# Sheet1.net
KiCad netlist of a schematic drawn in Altium Designer
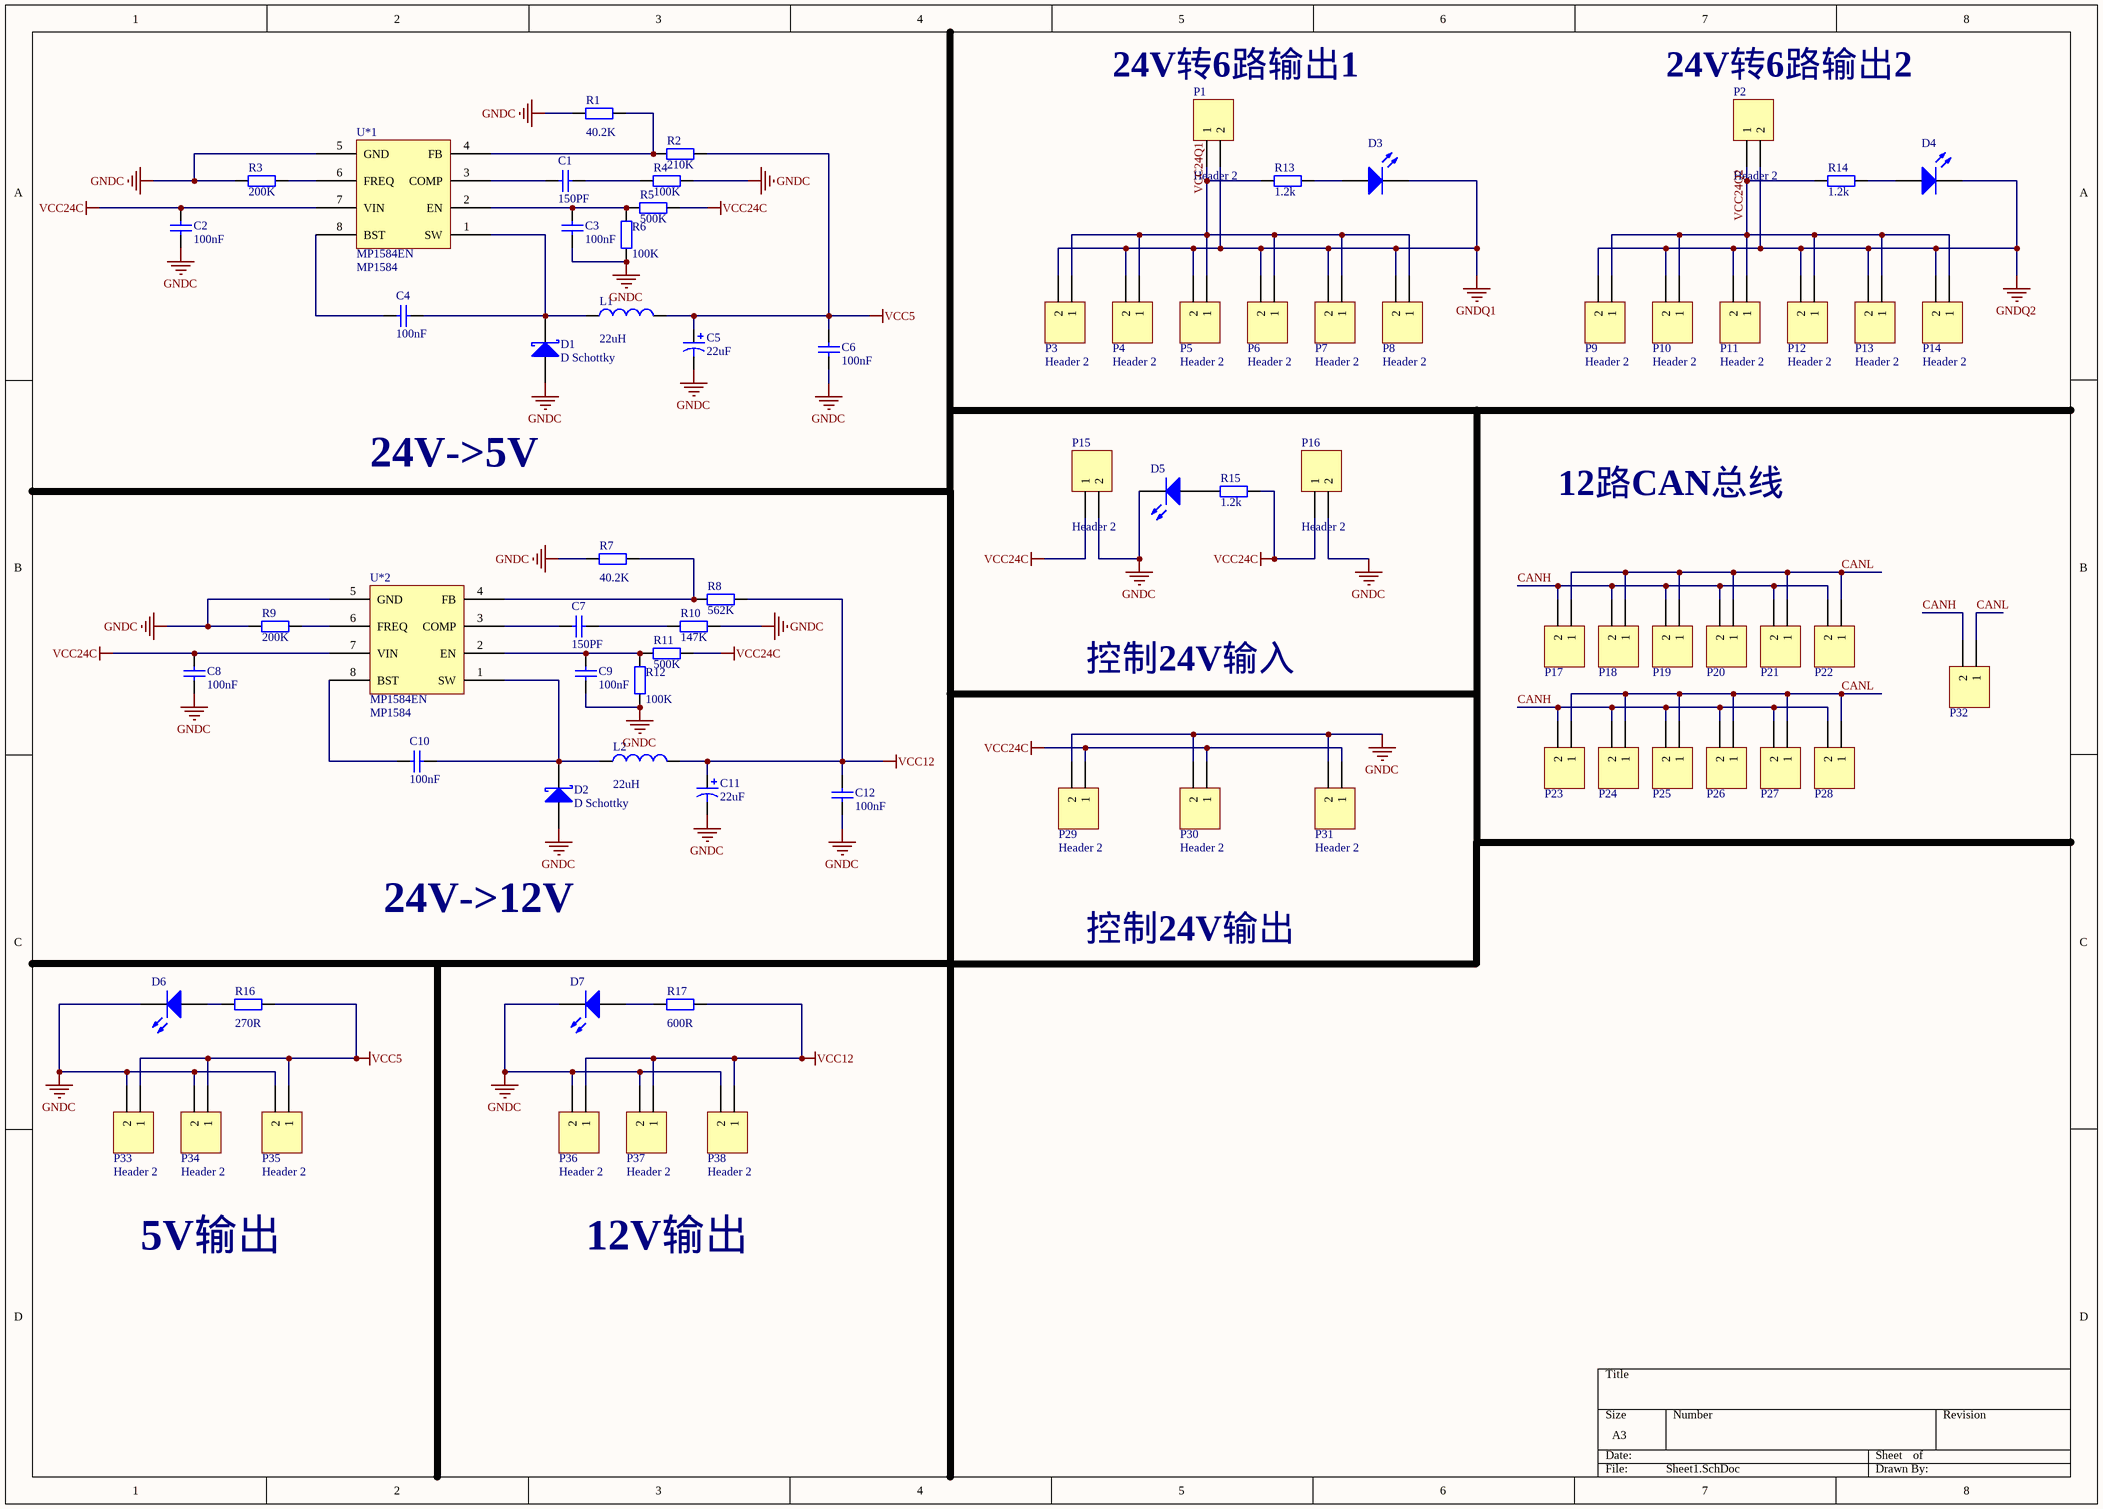
[diagram p0: Sheet1.SchDoc]

(export (version "E")
  (design (tool "Eeschema 10.0.6"))
  (components
    (comp (ref "C1")
      (value "150PF")
      (footprint "0603")
      (description "Capacitor")
      (fields (field (name "Comment") "Cap") (field (name "PUBLISHER") "Altium Limited"))
      (libsource (lib "Miscellaneous Devices") (part "Cap"))
    )
    (comp (ref "C2")
      (value "100nF")
      (footprint "0603")
      (description "Capacitor")
      (fields (field (name "Comment") "Cap") (field (name "PUBLISHER") "Altium Limited"))
      (libsource (lib "Miscellaneous Devices") (part "Cap"))
    )
    (comp (ref "C3")
      (value "100nF")
      (footprint "0603")
      (description "Capacitor")
      (fields (field (name "Comment") "Cap") (field (name "PUBLISHER") "Altium Limited"))
      (libsource (lib "Miscellaneous Devices") (part "Cap"))
    )
    (comp (ref "C4")
      (value "100nF")
      (footprint "0603")
      (description "Capacitor")
      (fields (field (name "Comment") "Cap") (field (name "PUBLISHER") "Altium Limited"))
      (libsource (lib "Miscellaneous Devices") (part "Cap"))
    )
    (comp (ref "C5")
      (value "22uF")
      (footprint "CAP_RVT1E220M0505")
      (description "Polarized Capacitor (Surface Mount)")
      (fields (field (name "Comment") "Cap Pol3") (field (name "PUBLISHER") "Altium Limited"))
      (libsource (lib "Miscellaneous Devices") (part "Cap Pol3"))
    )
    (comp (ref "C6")
      (value "100nF")
      (footprint "0603")
      (description "Capacitor")
      (fields (field (name "Comment") "Cap") (field (name "PUBLISHER") "Altium Limited"))
      (libsource (lib "Miscellaneous Devices") (part "Cap"))
    )
    (comp (ref "C7")
      (value "150PF")
      (footprint "0603")
      (description "Capacitor")
      (fields (field (name "Comment") "Cap") (field (name "PUBLISHER") "Altium Limited"))
      (libsource (lib "Miscellaneous Devices") (part "Cap"))
    )
    (comp (ref "C8")
      (value "100nF")
      (footprint "0603")
      (description "Capacitor")
      (fields (field (name "Comment") "Cap") (field (name "PUBLISHER") "Altium Limited"))
      (libsource (lib "Miscellaneous Devices") (part "Cap"))
    )
    (comp (ref "C9")
      (value "100nF")
      (footprint "0603")
      (description "Capacitor")
      (fields (field (name "Comment") "Cap") (field (name "PUBLISHER") "Altium Limited"))
      (libsource (lib "Miscellaneous Devices") (part "Cap"))
    )
    (comp (ref "C10")
      (value "100nF")
      (footprint "0603")
      (description "Capacitor")
      (fields (field (name "Comment") "Cap") (field (name "PUBLISHER") "Altium Limited"))
      (libsource (lib "Miscellaneous Devices") (part "Cap"))
    )
    (comp (ref "C11")
      (value "22uF")
      (footprint "CAP_RVT1E220M0505")
      (description "Polarized Capacitor (Surface Mount)")
      (fields (field (name "Comment") "Cap Pol3") (field (name "PUBLISHER") "Altium Limited"))
      (libsource (lib "Miscellaneous Devices") (part "Cap Pol3"))
    )
    (comp (ref "C12")
      (value "100nF")
      (footprint "0603")
      (description "Capacitor")
      (fields (field (name "Comment") "Cap") (field (name "PUBLISHER") "Altium Limited"))
      (libsource (lib "Miscellaneous Devices") (part "Cap"))
    )
    (comp (ref "D1")
      (value "D Schottky")
      (footprint "LC-SMB(DO-214AA)_S2")
      (description "Schottky Diode")
      (fields (field (name "PUBLISHER") "Altium Limited"))
      (libsource (lib "Miscellaneous Devices") (part "D Schottky"))
    )
    (comp (ref "D2")
      (value "D Schottky")
      (footprint "LC-SMB(DO-214AA)_S2")
      (description "Schottky Diode")
      (fields (field (name "PUBLISHER") "Altium Limited"))
      (libsource (lib "Miscellaneous Devices") (part "D Schottky"))
    )
    (comp (ref "D3")
      (value "LED0")
      (footprint "0603")
      (description "Typical INFRARED GaAs LED")
      (fields (field (name "PUBLISHER") "Altium Limited"))
      (libsource (lib "Miscellaneous Devices") (part "LED0"))
    )
    (comp (ref "D4")
      (value "LED0")
      (footprint "0603")
      (description "Typical INFRARED GaAs LED")
      (fields (field (name "PUBLISHER") "Altium Limited"))
      (libsource (lib "Miscellaneous Devices") (part "LED0"))
    )
    (comp (ref "D5")
      (value "LED0")
      (footprint "0603")
      (description "Typical INFRARED GaAs LED")
      (fields (field (name "PUBLISHER") "Altium Limited"))
      (libsource (lib "Miscellaneous Devices") (part "LED0"))
    )
    (comp (ref "D6")
      (value "LED0")
      (footprint "0603")
      (description "Typical INFRARED GaAs LED")
      (fields (field (name "PUBLISHER") "Altium Limited"))
      (libsource (lib "Miscellaneous Devices") (part "LED0"))
    )
    (comp (ref "D7")
      (value "LED0")
      (footprint "0603")
      (description "Typical INFRARED GaAs LED")
      (fields (field (name "PUBLISHER") "Altium Limited"))
      (libsource (lib "Miscellaneous Devices") (part "LED0"))
    )
    (comp (ref "L1")
      (value "22uH")
      (footprint "JSHC0650H220M")
      (description "Inductor")
      (fields (field (name "PUBLISHER") "Altium Limited"))
      (libsource (lib "Miscellaneous Devices") (part "Inductor"))
    )
    (comp (ref "L2")
      (value "22uH")
      (footprint "JSHC0650H220M")
      (description "Inductor")
      (fields (field (name "PUBLISHER") "Altium Limited"))
      (libsource (lib "Miscellaneous Devices") (part "Inductor"))
    )
    (comp (ref "P1")
      (value "Header 2")
      (footprint "TX60-LI-S")
      (description "Header, 2-Pin")
      (fields (field (name "PUBLISHER") "Altium Limited"))
      (libsource (lib "") (part "Header 2_1"))
    )
    (comp (ref "P2")
      (value "Header 2")
      (footprint "TX60-LI-S")
      (description "Header, 2-Pin")
      (fields (field (name "PUBLISHER") "Altium Limited"))
      (libsource (lib "") (part "Header 2_1"))
    )
    (comp (ref "P3")
      (value "Header 2")
      (footprint "XT30_LI")
      (description "Header, 2-Pin")
      (fields (field (name "PUBLISHER") "Altium Limited"))
      (libsource (lib "Miscellaneous Connectors") (part "Header 2"))
    )
    (comp (ref "P4")
      (value "Header 2")
      (footprint "XT30_LI")
      (description "Header, 2-Pin")
      (fields (field (name "PUBLISHER") "Altium Limited"))
      (libsource (lib "Miscellaneous Connectors") (part "Header 2"))
    )
    (comp (ref "P5")
      (value "Header 2")
      (footprint "XT30_LI")
      (description "Header, 2-Pin")
      (fields (field (name "PUBLISHER") "Altium Limited"))
      (libsource (lib "Miscellaneous Connectors") (part "Header 2"))
    )
    (comp (ref "P6")
      (value "Header 2")
      (footprint "XT30_LI")
      (description "Header, 2-Pin")
      (fields (field (name "PUBLISHER") "Altium Limited"))
      (libsource (lib "Miscellaneous Connectors") (part "Header 2"))
    )
    (comp (ref "P7")
      (value "Header 2")
      (footprint "XT30_LI")
      (description "Header, 2-Pin")
      (fields (field (name "PUBLISHER") "Altium Limited"))
      (libsource (lib "Miscellaneous Connectors") (part "Header 2"))
    )
    (comp (ref "P8")
      (value "Header 2")
      (footprint "XT30_LI")
      (description "Header, 2-Pin")
      (fields (field (name "PUBLISHER") "Altium Limited"))
      (libsource (lib "Miscellaneous Connectors") (part "Header 2"))
    )
    (comp (ref "P9")
      (value "Header 2")
      (footprint "XT30_LI")
      (description "Header, 2-Pin")
      (fields (field (name "PUBLISHER") "Altium Limited"))
      (libsource (lib "Miscellaneous Connectors") (part "Header 2"))
    )
    (comp (ref "P10")
      (value "Header 2")
      (footprint "XT30_LI")
      (description "Header, 2-Pin")
      (fields (field (name "PUBLISHER") "Altium Limited"))
      (libsource (lib "Miscellaneous Connectors") (part "Header 2"))
    )
    (comp (ref "P11")
      (value "Header 2")
      (footprint "XT30_LI")
      (description "Header, 2-Pin")
      (fields (field (name "PUBLISHER") "Altium Limited"))
      (libsource (lib "Miscellaneous Connectors") (part "Header 2"))
    )
    (comp (ref "P12")
      (value "Header 2")
      (footprint "XT30_LI")
      (description "Header, 2-Pin")
      (fields (field (name "PUBLISHER") "Altium Limited"))
      (libsource (lib "Miscellaneous Connectors") (part "Header 2"))
    )
    (comp (ref "P13")
      (value "Header 2")
      (footprint "XT30_LI")
      (description "Header, 2-Pin")
      (fields (field (name "PUBLISHER") "Altium Limited"))
      (libsource (lib "Miscellaneous Connectors") (part "Header 2"))
    )
    (comp (ref "P14")
      (value "Header 2")
      (footprint "XT30_LI")
      (description "Header, 2-Pin")
      (fields (field (name "PUBLISHER") "Altium Limited"))
      (libsource (lib "Miscellaneous Connectors") (part "Header 2"))
    )
    (comp (ref "P15")
      (value "Header 2")
      (footprint "TX60-LI-S")
      (description "Header, 2-Pin")
      (fields (field (name "PUBLISHER") "Altium Limited"))
      (libsource (lib "") (part "Header 2_1"))
    )
    (comp (ref "P16")
      (value "Header 2")
      (footprint "TX60-LI-S")
      (description "Header, 2-Pin")
      (fields (field (name "PUBLISHER") "Altium Limited"))
      (libsource (lib "") (part "Header 2_1"))
    )
    (comp (ref "P17")
      (value "Header 2")
      (footprint "GH1.25_2P")
      (description "Header, 2-Pin")
      (fields (field (name "PUBLISHER") "Altium Limited"))
      (libsource (lib "Miscellaneous Connectors") (part "Header 2"))
    )
    (comp (ref "P18")
      (value "Header 2")
      (footprint "GH1.25_2P")
      (description "Header, 2-Pin")
      (fields (field (name "PUBLISHER") "Altium Limited"))
      (libsource (lib "Miscellaneous Connectors") (part "Header 2"))
    )
    (comp (ref "P19")
      (value "Header 2")
      (footprint "GH1.25_2P")
      (description "Header, 2-Pin")
      (fields (field (name "PUBLISHER") "Altium Limited"))
      (libsource (lib "Miscellaneous Connectors") (part "Header 2"))
    )
    (comp (ref "P20")
      (value "Header 2")
      (footprint "GH1.25_2P")
      (description "Header, 2-Pin")
      (fields (field (name "PUBLISHER") "Altium Limited"))
      (libsource (lib "Miscellaneous Connectors") (part "Header 2"))
    )
    (comp (ref "P21")
      (value "Header 2")
      (footprint "GH1.25_2P")
      (description "Header, 2-Pin")
      (fields (field (name "PUBLISHER") "Altium Limited"))
      (libsource (lib "Miscellaneous Connectors") (part "Header 2"))
    )
    (comp (ref "P22")
      (value "Header 2")
      (footprint "GH1.25_2P")
      (description "Header, 2-Pin")
      (fields (field (name "PUBLISHER") "Altium Limited"))
      (libsource (lib "Miscellaneous Connectors") (part "Header 2"))
    )
    (comp (ref "P23")
      (value "Header 2")
      (footprint "GH1.25_2P")
      (description "Header, 2-Pin")
      (fields (field (name "PUBLISHER") "Altium Limited"))
      (libsource (lib "Miscellaneous Connectors") (part "Header 2"))
    )
    (comp (ref "P24")
      (value "Header 2")
      (footprint "GH1.25_2P")
      (description "Header, 2-Pin")
      (fields (field (name "PUBLISHER") "Altium Limited"))
      (libsource (lib "Miscellaneous Connectors") (part "Header 2"))
    )
    (comp (ref "P25")
      (value "Header 2")
      (footprint "GH1.25_2P")
      (description "Header, 2-Pin")
      (fields (field (name "PUBLISHER") "Altium Limited"))
      (libsource (lib "Miscellaneous Connectors") (part "Header 2"))
    )
    (comp (ref "P26")
      (value "Header 2")
      (footprint "GH1.25_2P")
      (description "Header, 2-Pin")
      (fields (field (name "PUBLISHER") "Altium Limited"))
      (libsource (lib "Miscellaneous Connectors") (part "Header 2"))
    )
    (comp (ref "P27")
      (value "Header 2")
      (footprint "GH1.25_2P")
      (description "Header, 2-Pin")
      (fields (field (name "PUBLISHER") "Altium Limited"))
      (libsource (lib "Miscellaneous Connectors") (part "Header 2"))
    )
    (comp (ref "P28")
      (value "Header 2")
      (footprint "GH1.25_2P")
      (description "Header, 2-Pin")
      (fields (field (name "PUBLISHER") "Altium Limited"))
      (libsource (lib "Miscellaneous Connectors") (part "Header 2"))
    )
    (comp (ref "P29")
      (value "Header 2")
      (footprint "XT30_LI")
      (description "Header, 2-Pin")
      (fields (field (name "PUBLISHER") "Altium Limited"))
      (libsource (lib "Miscellaneous Connectors") (part "Header 2"))
    )
    (comp (ref "P30")
      (value "Header 2")
      (footprint "XT30_LI")
      (description "Header, 2-Pin")
      (fields (field (name "PUBLISHER") "Altium Limited"))
      (libsource (lib "Miscellaneous Connectors") (part "Header 2"))
    )
    (comp (ref "P31")
      (value "Header 2")
      (footprint "XT30_LI")
      (description "Header, 2-Pin")
      (fields (field (name "PUBLISHER") "Altium Limited"))
      (libsource (lib "Miscellaneous Connectors") (part "Header 2"))
    )
    (comp (ref "P32")
      (value "Header 2")
      (footprint "GH1.25_2P")
      (description "Header, 2-Pin")
      (fields (field (name "PUBLISHER") "Altium Limited"))
      (libsource (lib "Miscellaneous Connectors") (part "Header 2"))
    )
    (comp (ref "P33")
      (value "Header 2")
      (footprint "XT30_LI")
      (description "Header, 2-Pin")
      (fields (field (name "PUBLISHER") "Altium Limited"))
      (libsource (lib "Miscellaneous Connectors") (part "Header 2"))
    )
    (comp (ref "P34")
      (value "Header 2")
      (footprint "XT30_LI")
      (description "Header, 2-Pin")
      (fields (field (name "PUBLISHER") "Altium Limited"))
      (libsource (lib "Miscellaneous Connectors") (part "Header 2"))
    )
    (comp (ref "P35")
      (value "Header 2")
      (footprint "XT30_LI")
      (description "Header, 2-Pin")
      (fields (field (name "PUBLISHER") "Altium Limited"))
      (libsource (lib "Miscellaneous Connectors") (part "Header 2"))
    )
    (comp (ref "P36")
      (value "Header 2")
      (footprint "XT30_LI")
      (description "Header, 2-Pin")
      (fields (field (name "PUBLISHER") "Altium Limited"))
      (libsource (lib "Miscellaneous Connectors") (part "Header 2"))
    )
    (comp (ref "P37")
      (value "Header 2")
      (footprint "XT30_LI")
      (description "Header, 2-Pin")
      (fields (field (name "PUBLISHER") "Altium Limited"))
      (libsource (lib "Miscellaneous Connectors") (part "Header 2"))
    )
    (comp (ref "P38")
      (value "Header 2")
      (footprint "XT30_LI")
      (description "Header, 2-Pin")
      (fields (field (name "PUBLISHER") "Altium Limited"))
      (libsource (lib "Miscellaneous Connectors") (part "Header 2"))
    )
    (comp (ref "R1")
      (value "40.2K")
      (footprint "0603")
      (description "Resistor")
      (fields (field (name "Comment") "Res2") (field (name "PUBLISHER") "Altium Limited"))
      (libsource (lib "") (part "Res2_1"))
    )
    (comp (ref "R2")
      (value "210K")
      (footprint "0603")
      (description "Resistor")
      (fields (field (name "Comment") "Res2") (field (name "PUBLISHER") "Altium Limited"))
      (libsource (lib "") (part "Res2_1"))
    )
    (comp (ref "R3")
      (value "200K")
      (footprint "0603")
      (description "Resistor")
      (fields (field (name "Comment") "Res2") (field (name "PUBLISHER") "Altium Limited"))
      (libsource (lib "") (part "Res2_1"))
    )
    (comp (ref "R4")
      (value "100K")
      (footprint "0603")
      (description "Resistor")
      (fields (field (name "Comment") "Res2") (field (name "PUBLISHER") "Altium Limited"))
      (libsource (lib "") (part "Res2_1"))
    )
    (comp (ref "R5")
      (value "500K")
      (footprint "0603")
      (description "Resistor")
      (fields (field (name "Comment") "Res2") (field (name "PUBLISHER") "Altium Limited"))
      (libsource (lib "") (part "Res2_1"))
    )
    (comp (ref "R6")
      (value "100K")
      (footprint "0603")
      (description "Resistor")
      (fields (field (name "Comment") "Res2") (field (name "PUBLISHER") "Altium Limited"))
      (libsource (lib "") (part "Res2_2"))
    )
    (comp (ref "R7")
      (value "40.2K")
      (footprint "0603")
      (description "Resistor")
      (fields (field (name "Comment") "Res2") (field (name "PUBLISHER") "Altium Limited"))
      (libsource (lib "") (part "Res2_1"))
    )
    (comp (ref "R8")
      (value "562K")
      (footprint "0603")
      (description "Resistor")
      (fields (field (name "Comment") "Res2") (field (name "PUBLISHER") "Altium Limited"))
      (libsource (lib "") (part "Res2_1"))
    )
    (comp (ref "R9")
      (value "200K")
      (footprint "0603")
      (description "Resistor")
      (fields (field (name "Comment") "Res2") (field (name "PUBLISHER") "Altium Limited"))
      (libsource (lib "") (part "Res2_1"))
    )
    (comp (ref "R10")
      (value "147K")
      (footprint "0603")
      (description "Resistor")
      (fields (field (name "Comment") "Res2") (field (name "PUBLISHER") "Altium Limited"))
      (libsource (lib "") (part "Res2_1"))
    )
    (comp (ref "R11")
      (value "500K")
      (footprint "0603")
      (description "Resistor")
      (fields (field (name "Comment") "Res2") (field (name "PUBLISHER") "Altium Limited"))
      (libsource (lib "") (part "Res2_1"))
    )
    (comp (ref "R12")
      (value "100K")
      (footprint "0603")
      (description "Resistor")
      (fields (field (name "Comment") "Res2") (field (name "PUBLISHER") "Altium Limited"))
      (libsource (lib "") (part "Res2_2"))
    )
    (comp (ref "R13")
      (value "1.2k")
      (footprint "0603")
      (description "Resistor")
      (fields (field (name "Comment") "Res2") (field (name "PUBLISHER") "Altium Limited"))
      (libsource (lib "Miscellaneous Devices") (part "Res2"))
    )
    (comp (ref "R14")
      (value "1.2k")
      (footprint "0603")
      (description "Resistor")
      (fields (field (name "Comment") "Res2") (field (name "PUBLISHER") "Altium Limited"))
      (libsource (lib "Miscellaneous Devices") (part "Res2"))
    )
    (comp (ref "R15")
      (value "1.2k")
      (footprint "0603")
      (description "Resistor")
      (fields (field (name "Comment") "Res2") (field (name "PUBLISHER") "Altium Limited"))
      (libsource (lib "") (part "Res2_1"))
    )
    (comp (ref "R16")
      (value "270R")
      (footprint "0603")
      (description "Resistor")
      (fields (field (name "Comment") "Res2") (field (name "PUBLISHER") "Altium Limited"))
      (libsource (lib "") (part "Res2_1"))
    )
    (comp (ref "R17")
      (value "600R")
      (footprint "0603")
      (description "Resistor")
      (fields (field (name "Comment") "Res2") (field (name "PUBLISHER") "Altium Limited"))
      (libsource (lib "") (part "Res2_1"))
    )
    (comp (ref "U*1")
      (value "MP1584")
      (footprint "MP1584EN_SOIC8E")
      (libsource (lib "Schlib1") (part "MP1584"))
    )
    (comp (ref "U*2")
      (value "MP1584")
      (footprint "MP1584EN_SOIC8E")
      (libsource (lib "Schlib1") (part "MP1584"))
    )
  )
  (nets
    (net (code "1") (name "/CANH") (class "Default")
      (node (ref "P17") (pin "2") (pinfunction "2_2") (pintype "passive"))
      (node (ref "P18") (pin "2") (pinfunction "2_2") (pintype "passive"))
      (node (ref "P19") (pin "2") (pinfunction "2_2") (pintype "passive"))
      (node (ref "P20") (pin "2") (pinfunction "2_2") (pintype "passive"))
      (node (ref "P21") (pin "2") (pinfunction "2_2") (pintype "passive"))
      (node (ref "P22") (pin "2") (pinfunction "2_2") (pintype "passive"))
      (node (ref "P23") (pin "2") (pinfunction "2_2") (pintype "passive"))
      (node (ref "P24") (pin "2") (pinfunction "2_2") (pintype "passive"))
      (node (ref "P25") (pin "2") (pinfunction "2_2") (pintype "passive"))
      (node (ref "P26") (pin "2") (pinfunction "2_2") (pintype "passive"))
      (node (ref "P27") (pin "2") (pinfunction "2_2") (pintype "passive"))
      (node (ref "P28") (pin "2") (pinfunction "2_2") (pintype "passive"))
      (node (ref "P32") (pin "2") (pinfunction "2_2") (pintype "passive"))
    )
    (net (code "2") (name "/CANL") (class "Default")
      (node (ref "P17") (pin "1") (pinfunction "1_1") (pintype "passive"))
      (node (ref "P18") (pin "1") (pinfunction "1_1") (pintype "passive"))
      (node (ref "P19") (pin "1") (pinfunction "1_1") (pintype "passive"))
      (node (ref "P20") (pin "1") (pinfunction "1_1") (pintype "passive"))
      (node (ref "P21") (pin "1") (pinfunction "1_1") (pintype "passive"))
      (node (ref "P22") (pin "1") (pinfunction "1_1") (pintype "passive"))
      (node (ref "P23") (pin "1") (pinfunction "1_1") (pintype "passive"))
      (node (ref "P24") (pin "1") (pinfunction "1_1") (pintype "passive"))
      (node (ref "P25") (pin "1") (pinfunction "1_1") (pintype "passive"))
      (node (ref "P26") (pin "1") (pinfunction "1_1") (pintype "passive"))
      (node (ref "P27") (pin "1") (pinfunction "1_1") (pintype "passive"))
      (node (ref "P28") (pin "1") (pinfunction "1_1") (pintype "passive"))
      (node (ref "P32") (pin "1") (pinfunction "1_1") (pintype "passive"))
    )
    (net (code "3") (name "/VCC24Q1") (class "Default")
      (node (ref "P1") (pin "1") (pinfunction "1_1") (pintype "passive"))
      (node (ref "P3") (pin "1") (pinfunction "1_1") (pintype "passive"))
      (node (ref "P4") (pin "1") (pinfunction "1_1") (pintype "passive"))
      (node (ref "P5") (pin "1") (pinfunction "1_1") (pintype "passive"))
      (node (ref "P6") (pin "1") (pinfunction "1_1") (pintype "passive"))
      (node (ref "P7") (pin "1") (pinfunction "1_1") (pintype "passive"))
      (node (ref "P8") (pin "1") (pinfunction "1_1") (pintype "passive"))
      (node (ref "R13") (pin "1") (pinfunction "1_1") (pintype "passive"))
    )
    (net (code "4") (name "/VCC24Q2") (class "Default")
      (node (ref "P10") (pin "1") (pinfunction "1_1") (pintype "passive"))
      (node (ref "P11") (pin "1") (pinfunction "1_1") (pintype "passive"))
      (node (ref "P12") (pin "1") (pinfunction "1_1") (pintype "passive"))
      (node (ref "P13") (pin "1") (pinfunction "1_1") (pintype "passive"))
      (node (ref "P14") (pin "1") (pinfunction "1_1") (pintype "passive"))
      (node (ref "P2") (pin "1") (pinfunction "1_1") (pintype "passive"))
      (node (ref "P9") (pin "1") (pinfunction "1_1") (pintype "passive"))
      (node (ref "R14") (pin "1") (pinfunction "1_1") (pintype "passive"))
    )
    (net (code "5") (name "GNDC") (class "Default")
      (node (ref "C11") (pin "2") (pinfunction "2_2") (pintype "passive"))
      (node (ref "C12") (pin "1") (pinfunction "1_1") (pintype "passive"))
      (node (ref "C2") (pin "1") (pinfunction "1_1") (pintype "passive"))
      (node (ref "C3") (pin "1") (pinfunction "1_1") (pintype "passive"))
      (node (ref "C5") (pin "2") (pinfunction "2_2") (pintype "passive"))
      (node (ref "C6") (pin "1") (pinfunction "1_1") (pintype "passive"))
      (node (ref "C8") (pin "1") (pinfunction "1_1") (pintype "passive"))
      (node (ref "C9") (pin "1") (pinfunction "1_1") (pintype "passive"))
      (node (ref "D1") (pin "1") (pinfunction "A_1") (pintype "passive"))
      (node (ref "D2") (pin "1") (pinfunction "A_1") (pintype "passive"))
      (node (ref "D5") (pin "2") (pinfunction "K_2") (pintype "passive"))
      (node (ref "D6") (pin "2") (pinfunction "K_2") (pintype "passive"))
      (node (ref "D7") (pin "2") (pinfunction "K_2") (pintype "passive"))
      (node (ref "P15") (pin "2") (pinfunction "2_2") (pintype "passive"))
      (node (ref "P16") (pin "2") (pinfunction "2_2") (pintype "passive"))
      (node (ref "P29") (pin "2") (pinfunction "2_2") (pintype "passive"))
      (node (ref "P30") (pin "2") (pinfunction "2_2") (pintype "passive"))
      (node (ref "P31") (pin "2") (pinfunction "2_2") (pintype "passive"))
      (node (ref "P33") (pin "2") (pinfunction "2_2") (pintype "passive"))
      (node (ref "P34") (pin "2") (pinfunction "2_2") (pintype "passive"))
      (node (ref "P35") (pin "2") (pinfunction "2_2") (pintype "passive"))
      (node (ref "P36") (pin "2") (pinfunction "2_2") (pintype "passive"))
      (node (ref "P37") (pin "2") (pinfunction "2_2") (pintype "passive"))
      (node (ref "P38") (pin "2") (pinfunction "2_2") (pintype "passive"))
      (node (ref "R1") (pin "2") (pinfunction "2_2") (pintype "passive"))
      (node (ref "R10") (pin "1") (pinfunction "1_1") (pintype "passive"))
      (node (ref "R12") (pin "1") (pinfunction "1_1") (pintype "passive"))
      (node (ref "R3") (pin "2") (pinfunction "2_2") (pintype "passive"))
      (node (ref "R4") (pin "1") (pinfunction "1_1") (pintype "passive"))
      (node (ref "R6") (pin "1") (pinfunction "1_1") (pintype "passive"))
      (node (ref "R7") (pin "2") (pinfunction "2_2") (pintype "passive"))
      (node (ref "R9") (pin "2") (pinfunction "2_2") (pintype "passive"))
      (node (ref "U*1") (pin "5") (pinfunction "GND_5") (pintype "passive"))
      (node (ref "U*2") (pin "5") (pinfunction "GND_5") (pintype "passive"))
    )
    (net (code "6") (name "GNDQ1") (class "Default")
      (node (ref "D3") (pin "2") (pinfunction "K_2") (pintype "passive"))
      (node (ref "P1") (pin "2") (pinfunction "2_2") (pintype "passive"))
      (node (ref "P3") (pin "2") (pinfunction "2_2") (pintype "passive"))
      (node (ref "P4") (pin "2") (pinfunction "2_2") (pintype "passive"))
      (node (ref "P5") (pin "2") (pinfunction "2_2") (pintype "passive"))
      (node (ref "P6") (pin "2") (pinfunction "2_2") (pintype "passive"))
      (node (ref "P7") (pin "2") (pinfunction "2_2") (pintype "passive"))
      (node (ref "P8") (pin "2") (pinfunction "2_2") (pintype "passive"))
    )
    (net (code "7") (name "GNDQ2") (class "Default")
      (node (ref "D4") (pin "2") (pinfunction "K_2") (pintype "passive"))
      (node (ref "P10") (pin "2") (pinfunction "2_2") (pintype "passive"))
      (node (ref "P11") (pin "2") (pinfunction "2_2") (pintype "passive"))
      (node (ref "P12") (pin "2") (pinfunction "2_2") (pintype "passive"))
      (node (ref "P13") (pin "2") (pinfunction "2_2") (pintype "passive"))
      (node (ref "P14") (pin "2") (pinfunction "2_2") (pintype "passive"))
      (node (ref "P2") (pin "2") (pinfunction "2_2") (pintype "passive"))
      (node (ref "P9") (pin "2") (pinfunction "2_2") (pintype "passive"))
    )
    (net (code "8") (name "Net-(C1-Pad1)") (class "Default")
      (node (ref "C1") (pin "1") (pinfunction "1_1") (pintype "passive"))
      (node (ref "R4") (pin "2") (pinfunction "2_2") (pintype "passive"))
    )
    (net (code "9") (name "Net-(C7-Pad1)") (class "Default")
      (node (ref "C7") (pin "1") (pinfunction "1_1") (pintype "passive"))
      (node (ref "R10") (pin "2") (pinfunction "2_2") (pintype "passive"))
    )
    (net (code "10") (name "Net-(D1-K)") (class "Default")
      (node (ref "C4") (pin "1") (pinfunction "1_1") (pintype "passive"))
      (node (ref "D1") (pin "2") (pinfunction "K_2") (pintype "passive"))
      (node (ref "L1") (pin "1") (pinfunction "1_1") (pintype "passive"))
      (node (ref "U*1") (pin "1") (pinfunction "SW_1") (pintype "passive"))
    )
    (net (code "11") (name "Net-(D2-K)") (class "Default")
      (node (ref "C10") (pin "1") (pinfunction "1_1") (pintype "passive"))
      (node (ref "D2") (pin "2") (pinfunction "K_2") (pintype "passive"))
      (node (ref "L2") (pin "1") (pinfunction "1_1") (pintype "passive"))
      (node (ref "U*2") (pin "1") (pinfunction "SW_1") (pintype "passive"))
    )
    (net (code "12") (name "Net-(D3-A)") (class "Default")
      (node (ref "D3") (pin "1") (pinfunction "A_1") (pintype "passive"))
      (node (ref "R13") (pin "2") (pinfunction "2_2") (pintype "passive"))
    )
    (net (code "13") (name "Net-(D4-A)") (class "Default")
      (node (ref "D4") (pin "1") (pinfunction "A_1") (pintype "passive"))
      (node (ref "R14") (pin "2") (pinfunction "2_2") (pintype "passive"))
    )
    (net (code "14") (name "Net-(D5-A)") (class "Default")
      (node (ref "D5") (pin "1") (pinfunction "A_1") (pintype "passive"))
      (node (ref "R15") (pin "2") (pinfunction "2_2") (pintype "passive"))
    )
    (net (code "15") (name "Net-(D6-A)") (class "Default")
      (node (ref "D6") (pin "1") (pinfunction "A_1") (pintype "passive"))
      (node (ref "R16") (pin "2") (pinfunction "2_2") (pintype "passive"))
    )
    (net (code "16") (name "Net-(D7-A)") (class "Default")
      (node (ref "D7") (pin "1") (pinfunction "A_1") (pintype "passive"))
      (node (ref "R17") (pin "2") (pinfunction "2_2") (pintype "passive"))
    )
    (net (code "17") (name "Net-(U*1-BST)") (class "Default")
      (node (ref "C4") (pin "2") (pinfunction "2_2") (pintype "passive"))
      (node (ref "U*1") (pin "8") (pinfunction "BST_8") (pintype "passive"))
    )
    (net (code "18") (name "Net-(U*1-COMP)") (class "Default")
      (node (ref "C1") (pin "2") (pinfunction "2_2") (pintype "passive"))
      (node (ref "U*1") (pin "3") (pinfunction "COMP_3") (pintype "passive"))
    )
    (net (code "19") (name "Net-(U*1-EN)") (class "Default")
      (node (ref "C3") (pin "2") (pinfunction "2_2") (pintype "passive"))
      (node (ref "R5") (pin "2") (pinfunction "2_2") (pintype "passive"))
      (node (ref "R6") (pin "2") (pinfunction "2_2") (pintype "passive"))
      (node (ref "U*1") (pin "2") (pinfunction "EN_2") (pintype "passive"))
    )
    (net (code "20") (name "Net-(U*1-FB)") (class "Default")
      (node (ref "R1") (pin "1") (pinfunction "1_1") (pintype "passive"))
      (node (ref "R2") (pin "2") (pinfunction "2_2") (pintype "passive"))
      (node (ref "U*1") (pin "4") (pinfunction "FB_4") (pintype "passive"))
    )
    (net (code "21") (name "Net-(U*1-FREQ)") (class "Default")
      (node (ref "R3") (pin "1") (pinfunction "1_1") (pintype "passive"))
      (node (ref "U*1") (pin "6") (pinfunction "FREQ_6") (pintype "passive"))
    )
    (net (code "22") (name "Net-(U*2-BST)") (class "Default")
      (node (ref "C10") (pin "2") (pinfunction "2_2") (pintype "passive"))
      (node (ref "U*2") (pin "8") (pinfunction "BST_8") (pintype "passive"))
    )
    (net (code "23") (name "Net-(U*2-COMP)") (class "Default")
      (node (ref "C7") (pin "2") (pinfunction "2_2") (pintype "passive"))
      (node (ref "U*2") (pin "3") (pinfunction "COMP_3") (pintype "passive"))
    )
    (net (code "24") (name "Net-(U*2-EN)") (class "Default")
      (node (ref "C9") (pin "2") (pinfunction "2_2") (pintype "passive"))
      (node (ref "R11") (pin "2") (pinfunction "2_2") (pintype "passive"))
      (node (ref "R12") (pin "2") (pinfunction "2_2") (pintype "passive"))
      (node (ref "U*2") (pin "2") (pinfunction "EN_2") (pintype "passive"))
    )
    (net (code "25") (name "Net-(U*2-FB)") (class "Default")
      (node (ref "R7") (pin "1") (pinfunction "1_1") (pintype "passive"))
      (node (ref "R8") (pin "2") (pinfunction "2_2") (pintype "passive"))
      (node (ref "U*2") (pin "4") (pinfunction "FB_4") (pintype "passive"))
    )
    (net (code "26") (name "Net-(U*2-FREQ)") (class "Default")
      (node (ref "R9") (pin "1") (pinfunction "1_1") (pintype "passive"))
      (node (ref "U*2") (pin "6") (pinfunction "FREQ_6") (pintype "passive"))
    )
    (net (code "27") (name "VCC5") (class "Default")
      (node (ref "C5") (pin "1") (pinfunction "1_1") (pintype "passive"))
      (node (ref "C6") (pin "2") (pinfunction "2_2") (pintype "passive"))
      (node (ref "L1") (pin "2") (pinfunction "2_2") (pintype "passive"))
      (node (ref "P33") (pin "1") (pinfunction "1_1") (pintype "passive"))
      (node (ref "P34") (pin "1") (pinfunction "1_1") (pintype "passive"))
      (node (ref "P35") (pin "1") (pinfunction "1_1") (pintype "passive"))
      (node (ref "R16") (pin "1") (pinfunction "1_1") (pintype "passive"))
      (node (ref "R2") (pin "1") (pinfunction "1_1") (pintype "passive"))
    )
    (net (code "28") (name "VCC12") (class "Default")
      (node (ref "C11") (pin "1") (pinfunction "1_1") (pintype "passive"))
      (node (ref "C12") (pin "2") (pinfunction "2_2") (pintype "passive"))
      (node (ref "L2") (pin "2") (pinfunction "2_2") (pintype "passive"))
      (node (ref "P36") (pin "1") (pinfunction "1_1") (pintype "passive"))
      (node (ref "P37") (pin "1") (pinfunction "1_1") (pintype "passive"))
      (node (ref "P38") (pin "1") (pinfunction "1_1") (pintype "passive"))
      (node (ref "R17") (pin "1") (pinfunction "1_1") (pintype "passive"))
      (node (ref "R8") (pin "1") (pinfunction "1_1") (pintype "passive"))
    )
    (net (code "29") (name "VCC24C") (class "Default")
      (node (ref "C2") (pin "2") (pinfunction "2_2") (pintype "passive"))
      (node (ref "C8") (pin "2") (pinfunction "2_2") (pintype "passive"))
      (node (ref "P15") (pin "1") (pinfunction "1_1") (pintype "passive"))
      (node (ref "P16") (pin "1") (pinfunction "1_1") (pintype "passive"))
      (node (ref "P29") (pin "1") (pinfunction "1_1") (pintype "passive"))
      (node (ref "P30") (pin "1") (pinfunction "1_1") (pintype "passive"))
      (node (ref "P31") (pin "1") (pinfunction "1_1") (pintype "passive"))
      (node (ref "R11") (pin "1") (pinfunction "1_1") (pintype "passive"))
      (node (ref "R15") (pin "1") (pinfunction "1_1") (pintype "passive"))
      (node (ref "R5") (pin "1") (pinfunction "1_1") (pintype "passive"))
      (node (ref "U*1") (pin "7") (pinfunction "VIN_7") (pintype "passive"))
      (node (ref "U*2") (pin "7") (pinfunction "VIN_7") (pintype "passive"))
    )
  )
)
